# BATTERIES_CONTROLLER.net
KiCad netlist of a schematic drawn in EAGLE
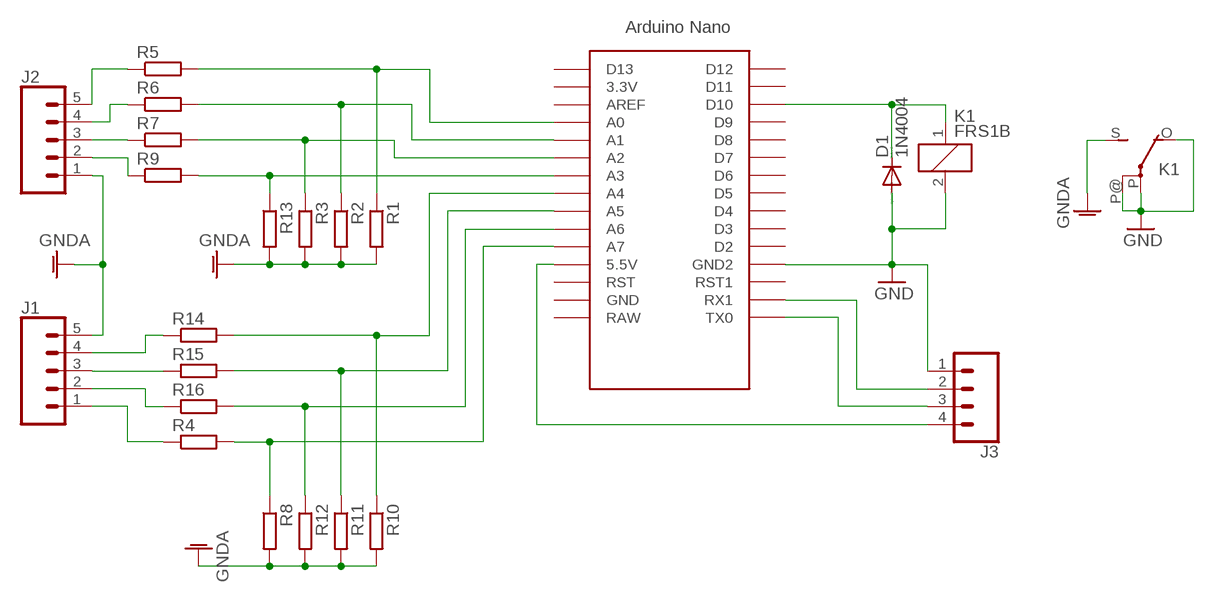
[diagram p0: schematic, sheet 1]

(export (version "E")
  (design (tool "Eeschema 10.0.6"))
  (components
    (comp (ref "D1")
      (value "1N4004")
      (footprint "eagle-import:DO41-10")
      (libsource (lib "eagle-import") (part "1N4004"))
    )
    (comp (ref "J1")
      (value "CONN_05")
      (footprint "eagle-import:1X05")
      (libsource (lib "eagle-import") (part "CONN_05"))
    )
    (comp (ref "J2")
      (value "CONN_05")
      (footprint "eagle-import:1X05")
      (libsource (lib "eagle-import") (part "CONN_05"))
    )
    (comp (ref "J3")
      (value "CONN_04")
      (footprint "eagle-import:1X04")
      (libsource (lib "eagle-import") (part "CONN_04"))
    )
    (comp (ref "K1")
      (value "FRS1B")
      (footprint "eagle-import:FRS1B")
      (libsource (lib "eagle-import") (part "FRS1B"))
    )
    (comp (ref "R1")
      (value "R-EU_M0805")
      (footprint "eagle-import:M0805")
      (libsource (lib "eagle-import") (part "R-EU_M0805"))
    )
    (comp (ref "R2")
      (value "R-EU_M0805")
      (footprint "eagle-import:M0805")
      (libsource (lib "eagle-import") (part "R-EU_M0805"))
    )
    (comp (ref "R3")
      (value "R-EU_M0805")
      (footprint "eagle-import:M0805")
      (libsource (lib "eagle-import") (part "R-EU_M0805"))
    )
    (comp (ref "R4")
      (value "R-EU_M0805")
      (footprint "eagle-import:M0805")
      (libsource (lib "eagle-import") (part "R-EU_M0805"))
    )
    (comp (ref "R5")
      (value "R-EU_M0805")
      (footprint "eagle-import:M0805")
      (libsource (lib "eagle-import") (part "R-EU_M0805"))
    )
    (comp (ref "R6")
      (value "R-EU_M0805")
      (footprint "eagle-import:M0805")
      (libsource (lib "eagle-import") (part "R-EU_M0805"))
    )
    (comp (ref "R7")
      (value "R-EU_M0805")
      (footprint "eagle-import:M0805")
      (libsource (lib "eagle-import") (part "R-EU_M0805"))
    )
    (comp (ref "R8")
      (value "R-EU_M0805")
      (footprint "eagle-import:M0805")
      (libsource (lib "eagle-import") (part "R-EU_M0805"))
    )
    (comp (ref "R9")
      (value "R-EU_M0805")
      (footprint "eagle-import:M0805")
      (libsource (lib "eagle-import") (part "R-EU_M0805"))
    )
    (comp (ref "R10")
      (value "R-EU_M0805")
      (footprint "eagle-import:M0805")
      (libsource (lib "eagle-import") (part "R-EU_M0805"))
    )
    (comp (ref "R11")
      (value "R-EU_M0805")
      (footprint "eagle-import:M0805")
      (libsource (lib "eagle-import") (part "R-EU_M0805"))
    )
    (comp (ref "R12")
      (value "R-EU_M0805")
      (footprint "eagle-import:M0805")
      (libsource (lib "eagle-import") (part "R-EU_M0805"))
    )
    (comp (ref "R13")
      (value "R-EU_M0805")
      (footprint "eagle-import:M0805")
      (libsource (lib "eagle-import") (part "R-EU_M0805"))
    )
    (comp (ref "R14")
      (value "R-EU_M0805")
      (footprint "eagle-import:M0805")
      (libsource (lib "eagle-import") (part "R-EU_M0805"))
    )
    (comp (ref "R15")
      (value "R-EU_M0805")
      (footprint "eagle-import:M0805")
      (libsource (lib "eagle-import") (part "R-EU_M0805"))
    )
    (comp (ref "R16")
      (value "R-EU_M0805")
      (footprint "eagle-import:M0805")
      (libsource (lib "eagle-import") (part "R-EU_M0805"))
    )
    (comp (ref "U$1")
      (value "NANO")
      (footprint "eagle-import:NANO")
      (libsource (lib "eagle-import") (part "NANO"))
    )
  )
  (nets
    (net (code "1") (name "GND") (class "Default")
      (node (ref "D1") (pin "A") (pinfunction "A_A") (pintype "passive"))
      (node (ref "J3") (pin "1") (pinfunction "1_1") (pintype "passive"))
      (node (ref "K1") (pin "2") (pinfunction "2_2") (pintype "passive"))
      (node (ref "K1") (pin "O") (pinfunction "O_O") (pintype "passive"))
      (node (ref "K1") (pin "P") (pinfunction "P_P") (pintype "passive"))
      (node (ref "K1") (pin "P@") (pinfunction "P_P@") (pintype "passive"))
      (node (ref "U$1") (pin "GND1") (pinfunction "GND2_GND1") (pintype "bidirectional"))
    )
    (net (code "2") (name "GNDA") (class "Default")
      (node (ref "J1") (pin "5") (pinfunction "5_5") (pintype "passive"))
      (node (ref "J2") (pin "1") (pinfunction "1_1") (pintype "passive"))
      (node (ref "K1") (pin "S") (pinfunction "S_S") (pintype "passive"))
      (node (ref "R1") (pin "2") (pinfunction "2_2") (pintype "passive"))
      (node (ref "R10") (pin "2") (pinfunction "2_2") (pintype "passive"))
      (node (ref "R11") (pin "2") (pinfunction "2_2") (pintype "passive"))
      (node (ref "R12") (pin "2") (pinfunction "2_2") (pintype "passive"))
      (node (ref "R13") (pin "2") (pinfunction "2_2") (pintype "passive"))
      (node (ref "R2") (pin "2") (pinfunction "2_2") (pintype "passive"))
      (node (ref "R3") (pin "2") (pinfunction "2_2") (pintype "passive"))
      (node (ref "R8") (pin "2") (pinfunction "2_2") (pintype "passive"))
    )
    (net (code "3") (name "Net-(D1-PadC)") (class "Default")
      (node (ref "D1") (pin "C") (pinfunction "C_C") (pintype "passive"))
      (node (ref "K1") (pin "1") (pinfunction "1_1") (pintype "passive"))
      (node (ref "U$1") (pin "D10") (pinfunction "D10_D10") (pintype "bidirectional"))
    )
    (net (code "4") (name "Net-(J1-Pad1)") (class "Default")
      (node (ref "J1") (pin "1") (pinfunction "1_1") (pintype "passive"))
      (node (ref "R4") (pin "1") (pinfunction "1_1") (pintype "passive"))
    )
    (net (code "5") (name "Net-(J1-Pad2)") (class "Default")
      (node (ref "J1") (pin "2") (pinfunction "2_2") (pintype "passive"))
      (node (ref "R16") (pin "1") (pinfunction "1_1") (pintype "passive"))
    )
    (net (code "6") (name "Net-(J1-Pad3)") (class "Default")
      (node (ref "J1") (pin "3") (pinfunction "3_3") (pintype "passive"))
      (node (ref "R15") (pin "1") (pinfunction "1_1") (pintype "passive"))
    )
    (net (code "7") (name "Net-(J1-Pad4)") (class "Default")
      (node (ref "J1") (pin "4") (pinfunction "4_4") (pintype "passive"))
      (node (ref "R14") (pin "1") (pinfunction "1_1") (pintype "passive"))
    )
    (net (code "8") (name "Net-(J2-Pad2)") (class "Default")
      (node (ref "J2") (pin "2") (pinfunction "2_2") (pintype "passive"))
      (node (ref "R9") (pin "1") (pinfunction "1_1") (pintype "passive"))
    )
    (net (code "9") (name "Net-(J2-Pad3)") (class "Default")
      (node (ref "J2") (pin "3") (pinfunction "3_3") (pintype "passive"))
      (node (ref "R7") (pin "1") (pinfunction "1_1") (pintype "passive"))
    )
    (net (code "10") (name "Net-(J2-Pad4)") (class "Default")
      (node (ref "J2") (pin "4") (pinfunction "4_4") (pintype "passive"))
      (node (ref "R6") (pin "1") (pinfunction "1_1") (pintype "passive"))
    )
    (net (code "11") (name "Net-(J2-Pad5)") (class "Default")
      (node (ref "J2") (pin "5") (pinfunction "5_5") (pintype "passive"))
      (node (ref "R5") (pin "1") (pinfunction "1_1") (pintype "passive"))
    )
    (net (code "12") (name "Net-(J3-Pad2)") (class "Default")
      (node (ref "J3") (pin "2") (pinfunction "2_2") (pintype "passive"))
      (node (ref "U$1") (pin "RX1") (pinfunction "RX1_RX1") (pintype "bidirectional"))
    )
    (net (code "13") (name "Net-(J3-Pad3)") (class "Default")
      (node (ref "J3") (pin "3") (pinfunction "3_3") (pintype "passive"))
      (node (ref "U$1") (pin "TX0") (pinfunction "TX0_TX0") (pintype "bidirectional"))
    )
    (net (code "14") (name "Net-(R1-Pad1)") (class "Default")
      (node (ref "R1") (pin "1") (pinfunction "1_1") (pintype "passive"))
      (node (ref "R5") (pin "2") (pinfunction "2_2") (pintype "passive"))
      (node (ref "U$1") (pin "A0") (pinfunction "A0_A0") (pintype "bidirectional"))
    )
    (net (code "15") (name "Net-(R2-Pad1)") (class "Default")
      (node (ref "R2") (pin "1") (pinfunction "1_1") (pintype "passive"))
      (node (ref "R6") (pin "2") (pinfunction "2_2") (pintype "passive"))
      (node (ref "U$1") (pin "A1") (pinfunction "A1_A1") (pintype "bidirectional"))
    )
    (net (code "16") (name "Net-(R3-Pad1)") (class "Default")
      (node (ref "R3") (pin "1") (pinfunction "1_1") (pintype "passive"))
      (node (ref "R7") (pin "2") (pinfunction "2_2") (pintype "passive"))
      (node (ref "U$1") (pin "A2") (pinfunction "A2_A2") (pintype "bidirectional"))
    )
    (net (code "17") (name "Net-(R4-Pad2)") (class "Default")
      (node (ref "R4") (pin "2") (pinfunction "2_2") (pintype "passive"))
      (node (ref "R8") (pin "1") (pinfunction "1_1") (pintype "passive"))
      (node (ref "U$1") (pin "A7") (pinfunction "A7_A7") (pintype "bidirectional"))
    )
    (net (code "18") (name "Net-(R10-Pad1)") (class "Default")
      (node (ref "R10") (pin "1") (pinfunction "1_1") (pintype "passive"))
      (node (ref "R14") (pin "2") (pinfunction "2_2") (pintype "passive"))
      (node (ref "U$1") (pin "A4") (pinfunction "A4_A4") (pintype "bidirectional"))
    )
    (net (code "19") (name "Net-(R11-Pad1)") (class "Default")
      (node (ref "R11") (pin "1") (pinfunction "1_1") (pintype "passive"))
      (node (ref "R15") (pin "2") (pinfunction "2_2") (pintype "passive"))
      (node (ref "U$1") (pin "A5") (pinfunction "A5_A5") (pintype "bidirectional"))
    )
    (net (code "20") (name "Net-(R12-Pad1)") (class "Default")
      (node (ref "R12") (pin "1") (pinfunction "1_1") (pintype "passive"))
      (node (ref "R16") (pin "2") (pinfunction "2_2") (pintype "passive"))
      (node (ref "U$1") (pin "A6") (pinfunction "A6_A6") (pintype "bidirectional"))
    )
    (net (code "21") (name "Net-(R13-Pad1)") (class "Default")
      (node (ref "R13") (pin "1") (pinfunction "1_1") (pintype "passive"))
      (node (ref "R9") (pin "2") (pinfunction "2_2") (pintype "passive"))
      (node (ref "U$1") (pin "A3") (pinfunction "A3_A3") (pintype "bidirectional"))
    )
    (net (code "22") (name "Net-(U$1-5.5V)") (class "Default")
      (node (ref "J3") (pin "4") (pinfunction "4_4") (pintype "passive"))
      (node (ref "U$1") (pin "5V") (pinfunction "5.5V_5V") (pintype "bidirectional"))
    )
    (net (code "23") (name "unconnected-(U$1-Pad3.3V)") (class "Default")
      (node (ref "U$1") (pin "3.3V") (pinfunction "3.3V_3.3V") (pintype "bidirectional"))
    )
    (net (code "24") (name "unconnected-(U$1-PadAREF)") (class "Default")
      (node (ref "U$1") (pin "AREF") (pinfunction "AREF_AREF") (pintype "bidirectional"))
    )
    (net (code "25") (name "unconnected-(U$1-PadD2)") (class "Default")
      (node (ref "U$1") (pin "D2") (pinfunction "D2_D2") (pintype "bidirectional"))
    )
    (net (code "26") (name "unconnected-(U$1-PadD3)") (class "Default")
      (node (ref "U$1") (pin "D3") (pinfunction "D3_D3") (pintype "bidirectional"))
    )
    (net (code "27") (name "unconnected-(U$1-PadD4)") (class "Default")
      (node (ref "U$1") (pin "D4") (pinfunction "D4_D4") (pintype "bidirectional"))
    )
    (net (code "28") (name "unconnected-(U$1-PadD5)") (class "Default")
      (node (ref "U$1") (pin "D5") (pinfunction "D5_D5") (pintype "bidirectional"))
    )
    (net (code "29") (name "unconnected-(U$1-PadD6)") (class "Default")
      (node (ref "U$1") (pin "D6") (pinfunction "D6_D6") (pintype "bidirectional"))
    )
    (net (code "30") (name "unconnected-(U$1-PadD7)") (class "Default")
      (node (ref "U$1") (pin "D7") (pinfunction "D7_D7") (pintype "bidirectional"))
    )
    (net (code "31") (name "unconnected-(U$1-PadD8)") (class "Default")
      (node (ref "U$1") (pin "D8") (pinfunction "D8_D8") (pintype "bidirectional"))
    )
    (net (code "32") (name "unconnected-(U$1-PadD9)") (class "Default")
      (node (ref "U$1") (pin "D9") (pinfunction "D9_D9") (pintype "bidirectional"))
    )
    (net (code "33") (name "unconnected-(U$1-PadD11)") (class "Default")
      (node (ref "U$1") (pin "D11") (pinfunction "D11_D11") (pintype "bidirectional"))
    )
    (net (code "34") (name "unconnected-(U$1-PadD12)") (class "Default")
      (node (ref "U$1") (pin "D12") (pinfunction "D12_D12") (pintype "bidirectional"))
    )
    (net (code "35") (name "unconnected-(U$1-PadD13)") (class "Default")
      (node (ref "U$1") (pin "D13") (pinfunction "D13_D13") (pintype "bidirectional"))
    )
    (net (code "36") (name "unconnected-(U$1-PadGND)") (class "Default")
      (node (ref "U$1") (pin "GND") (pinfunction "GND_GND") (pintype "bidirectional"))
    )
    (net (code "37") (name "unconnected-(U$1-PadICSP1)") (class "Default")
      (node (ref "U$1") (pin "ICSP1") (pinfunction "ICSP1_ICSP1") (pintype "bidirectional"))
    )
    (net (code "38") (name "unconnected-(U$1-PadICSP2)") (class "Default")
      (node (ref "U$1") (pin "ICSP2") (pinfunction "ICSP2_ICSP2") (pintype "bidirectional"))
    )
    (net (code "39") (name "unconnected-(U$1-PadICSP3)") (class "Default")
      (node (ref "U$1") (pin "ICSP3") (pinfunction "ICSP3_ICSP3") (pintype "bidirectional"))
    )
    (net (code "40") (name "unconnected-(U$1-PadICSP4)") (class "Default")
      (node (ref "U$1") (pin "ICSP4") (pinfunction "ICSP4_ICSP4") (pintype "bidirectional"))
    )
    (net (code "41") (name "unconnected-(U$1-PadICSP5)") (class "Default")
      (node (ref "U$1") (pin "ICSP5") (pinfunction "ICSP5_ICSP5") (pintype "bidirectional"))
    )
    (net (code "42") (name "unconnected-(U$1-PadICSP6)") (class "Default")
      (node (ref "U$1") (pin "ICSP6") (pinfunction "ICSP6_ICSP6") (pintype "bidirectional"))
    )
    (net (code "43") (name "unconnected-(U$1-PadRAW)") (class "Default")
      (node (ref "U$1") (pin "RAW") (pinfunction "RAW_RAW") (pintype "bidirectional"))
    )
    (net (code "44") (name "unconnected-(U$1-PadRST)") (class "Default")
      (node (ref "U$1") (pin "RST") (pinfunction "RST_RST") (pintype "bidirectional"))
    )
    (net (code "45") (name "unconnected-(U$1-PadRST1)") (class "Default")
      (node (ref "U$1") (pin "RST1") (pinfunction "RST1_RST1") (pintype "bidirectional"))
    )
  )
)
